# l-drv_h2-smd-001.net
KiCad netlist of a schematic drawn in EAGLE
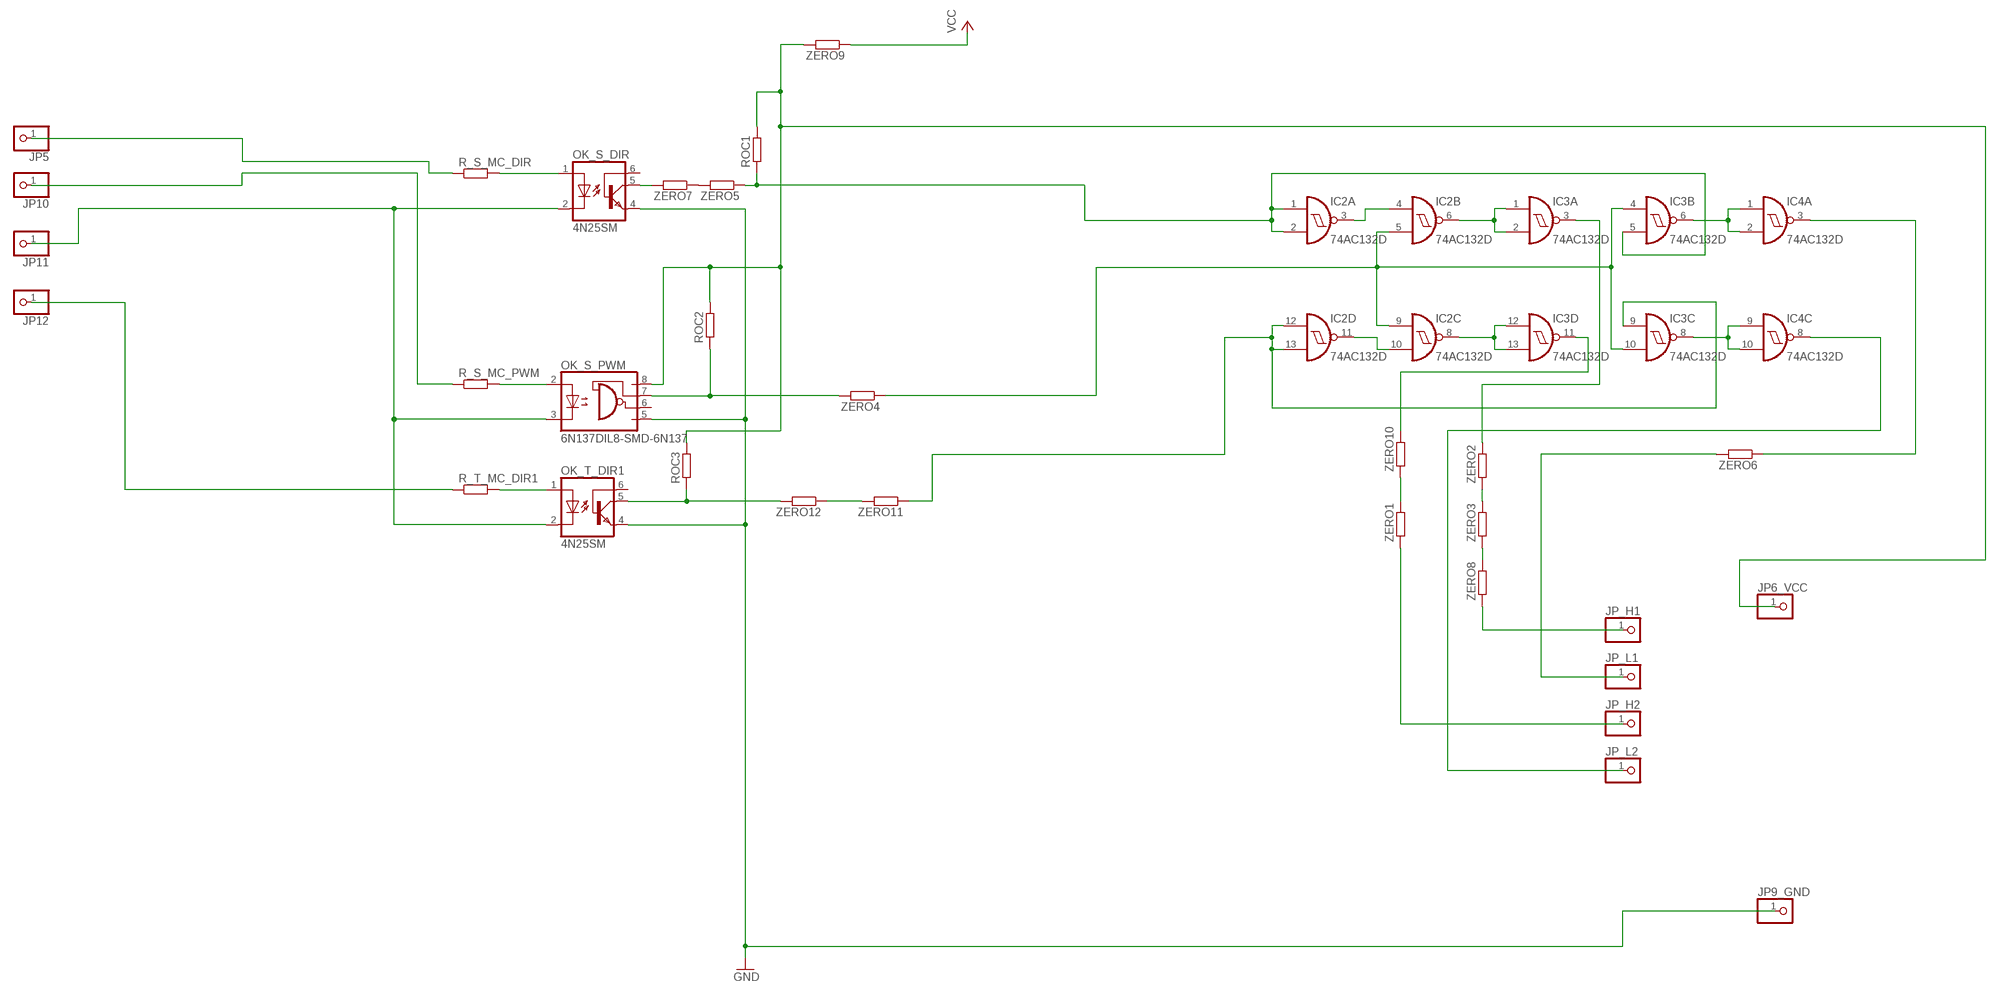
[diagram p0: schematic, sheet 1]

(export (version "E")
  (design (tool "Eeschema 10.0.6"))
  (components
    (comp (ref "IC2")
      (value "74AC132D")
      (footprint "eagle-import:SO14")
      (libsource (lib "eagle-import") (part "74132DAC"))
    )
    (comp (ref "IC3")
      (value "74AC132D")
      (footprint "eagle-import:SO14")
      (libsource (lib "eagle-import") (part "74132DAC"))
    )
    (comp (ref "IC4")
      (value "74AC132D")
      (footprint "eagle-import:SO14")
      (libsource (lib "eagle-import") (part "74132DAC"))
    )
    (comp (ref "JP5")
      (value "PINHD-1X1")
      (footprint "eagle-import:1X01")
      (libsource (lib "eagle-import") (part "PINHD-1X1"))
    )
    (comp (ref "JP6_VCC")
      (value "PINHD-1X1")
      (footprint "eagle-import:1X01")
      (libsource (lib "eagle-import") (part "PINHD-1X1"))
    )
    (comp (ref "JP9_GND")
      (value "PINHD-1X1")
      (footprint "eagle-import:1X01")
      (libsource (lib "eagle-import") (part "PINHD-1X1"))
    )
    (comp (ref "JP10")
      (value "PINHD-1X1")
      (footprint "eagle-import:1X01")
      (libsource (lib "eagle-import") (part "PINHD-1X1"))
    )
    (comp (ref "JP11")
      (value "PINHD-1X1")
      (footprint "eagle-import:1X01")
      (libsource (lib "eagle-import") (part "PINHD-1X1"))
    )
    (comp (ref "JP12")
      (value "PINHD-1X1")
      (footprint "eagle-import:1X01")
      (libsource (lib "eagle-import") (part "PINHD-1X1"))
    )
    (comp (ref "JP_H1")
      (value "PINHD-1X1")
      (footprint "eagle-import:1X01")
      (libsource (lib "eagle-import") (part "PINHD-1X1"))
    )
    (comp (ref "JP_H2")
      (value "PINHD-1X1")
      (footprint "eagle-import:1X01")
      (libsource (lib "eagle-import") (part "PINHD-1X1"))
    )
    (comp (ref "JP_L1")
      (value "PINHD-1X1")
      (footprint "eagle-import:1X01")
      (libsource (lib "eagle-import") (part "PINHD-1X1"))
    )
    (comp (ref "JP_L2")
      (value "PINHD-1X1")
      (footprint "eagle-import:1X01")
      (libsource (lib "eagle-import") (part "PINHD-1X1"))
    )
    (comp (ref "OK_S_DIR")
      (value "4N25SM")
      (footprint "eagle-import:DIL6-SMD")
      (fields (field (name "MF") "FAIRCHILD SEMICONDUCTOR"))
      (libsource (lib "eagle-import") (part "4N?MS25"))
    )
    (comp (ref "OK_S_PWM")
      (value "6N137DIL8-SMD-6N137")
      (footprint "eagle-import:DIL8-SMD")
      (libsource (lib "eagle-import") (part "6N137DIL8-SMD-6N137"))
    )
    (comp (ref "OK_T_DIR1")
      (value "4N25SM")
      (footprint "eagle-import:DIL6-SMD")
      (fields (field (name "MF") "FAIRCHILD SEMICONDUCTOR"))
      (libsource (lib "eagle-import") (part "4N?MS25"))
    )
    (comp (ref "ROC1")
      (value "R-EU_R1206")
      (footprint "eagle-import:R1206")
      (libsource (lib "eagle-import") (part "R-EU_R1206"))
    )
    (comp (ref "ROC2")
      (value "R-EU_R1206")
      (footprint "eagle-import:R1206")
      (libsource (lib "eagle-import") (part "R-EU_R1206"))
    )
    (comp (ref "ROC3")
      (value "R-EU_R1206")
      (footprint "eagle-import:R1206")
      (libsource (lib "eagle-import") (part "R-EU_R1206"))
    )
    (comp (ref "R_S_MC_DIR")
      (value "R-EU_R1206")
      (footprint "eagle-import:R1206")
      (libsource (lib "eagle-import") (part "R-EU_R1206"))
    )
    (comp (ref "R_S_MC_PWM")
      (value "R-EU_R1206")
      (footprint "eagle-import:R1206")
      (libsource (lib "eagle-import") (part "R-EU_R1206"))
    )
    (comp (ref "R_T_MC_DIR1")
      (value "R-EU_R1206")
      (footprint "eagle-import:R1206")
      (libsource (lib "eagle-import") (part "R-EU_R1206"))
    )
    (comp (ref "ZERO1")
      (value "R-EU_R1206")
      (footprint "eagle-import:R1206")
      (libsource (lib "eagle-import") (part "R-EU_R1206"))
    )
    (comp (ref "ZERO2")
      (value "R-EU_R1206")
      (footprint "eagle-import:R1206")
      (libsource (lib "eagle-import") (part "R-EU_R1206"))
    )
    (comp (ref "ZERO3")
      (value "R-EU_R1206")
      (footprint "eagle-import:R1206")
      (libsource (lib "eagle-import") (part "R-EU_R1206"))
    )
    (comp (ref "ZERO4")
      (value "R-EU_R1206")
      (footprint "eagle-import:R1206")
      (libsource (lib "eagle-import") (part "R-EU_R1206"))
    )
    (comp (ref "ZERO5")
      (value "R-EU_R1206")
      (footprint "eagle-import:R1206")
      (libsource (lib "eagle-import") (part "R-EU_R1206"))
    )
    (comp (ref "ZERO6")
      (value "R-EU_R1206")
      (footprint "eagle-import:R1206")
      (libsource (lib "eagle-import") (part "R-EU_R1206"))
    )
    (comp (ref "ZERO7")
      (value "R-EU_R1206")
      (footprint "eagle-import:R1206")
      (libsource (lib "eagle-import") (part "R-EU_R1206"))
    )
    (comp (ref "ZERO8")
      (value "R-EU_R1206")
      (footprint "eagle-import:R1206")
      (libsource (lib "eagle-import") (part "R-EU_R1206"))
    )
    (comp (ref "ZERO9")
      (value "R-EU_R1206")
      (footprint "eagle-import:R1206")
      (libsource (lib "eagle-import") (part "R-EU_R1206"))
    )
    (comp (ref "ZERO10")
      (value "R-EU_R1206")
      (footprint "eagle-import:R1206")
      (libsource (lib "eagle-import") (part "R-EU_R1206"))
    )
    (comp (ref "ZERO11")
      (value "R-EU_R1206")
      (footprint "eagle-import:R1206")
      (libsource (lib "eagle-import") (part "R-EU_R1206"))
    )
    (comp (ref "ZERO12")
      (value "R-EU_R1206")
      (footprint "eagle-import:R1206")
      (libsource (lib "eagle-import") (part "R-EU_R1206"))
    )
  )
  (nets
    (net (code "1") (name "GND") (class "Default")
      (node (ref "JP9_GND") (pin "1") (pinfunction "1_1") (pintype "passive"))
      (node (ref "OK_S_DIR") (pin "4") (pinfunction "EMI_4") (pintype "passive"))
      (node (ref "OK_S_PWM") (pin "5") (pinfunction "GND_5") (pintype "passive"))
      (node (ref "OK_T_DIR1") (pin "4") (pinfunction "EMI_4") (pintype "passive"))
    )
    (net (code "2") (name "Net-(IC2A-I0)") (class "Default")
      (node (ref "IC2") (pin "1") (pinfunction "I0_1") (pintype "input"))
      (node (ref "IC2") (pin "2") (pinfunction "I1_2") (pintype "input"))
      (node (ref "IC3") (pin "5") (pinfunction "I1_5") (pintype "input"))
      (node (ref "ROC1") (pin "1") (pinfunction "1_1") (pintype "passive"))
      (node (ref "ZERO5") (pin "1") (pinfunction "1_1") (pintype "passive"))
    )
    (net (code "3") (name "Net-(IC2A-O)") (class "Default")
      (node (ref "IC2") (pin "3") (pinfunction "O_3") (pintype "output"))
      (node (ref "IC2") (pin "4") (pinfunction "I0_4") (pintype "input"))
    )
    (net (code "4") (name "Net-(IC2B-I1)") (class "Default")
      (node (ref "IC2") (pin "5") (pinfunction "I1_5") (pintype "input"))
      (node (ref "IC2") (pin "9") (pinfunction "I0_9") (pintype "input"))
      (node (ref "IC3") (pin "10") (pinfunction "I1_10") (pintype "input"))
      (node (ref "IC3") (pin "4") (pinfunction "I0_4") (pintype "input"))
      (node (ref "ZERO4") (pin "1") (pinfunction "1_1") (pintype "passive"))
    )
    (net (code "5") (name "Net-(IC2B-O)") (class "Default")
      (node (ref "IC2") (pin "6") (pinfunction "O_6") (pintype "output"))
      (node (ref "IC3") (pin "1") (pinfunction "I0_1") (pintype "input"))
      (node (ref "IC3") (pin "2") (pinfunction "I1_2") (pintype "input"))
    )
    (net (code "6") (name "Net-(IC2C-I1)") (class "Default")
      (node (ref "IC2") (pin "10") (pinfunction "I1_10") (pintype "input"))
      (node (ref "IC2") (pin "11") (pinfunction "O_11") (pintype "output"))
    )
    (net (code "7") (name "Net-(IC2C-O)") (class "Default")
      (node (ref "IC2") (pin "8") (pinfunction "O_8") (pintype "output"))
      (node (ref "IC3") (pin "12") (pinfunction "I0_12") (pintype "input"))
      (node (ref "IC3") (pin "13") (pinfunction "I1_13") (pintype "input"))
    )
    (net (code "8") (name "Net-(IC2D-I0)") (class "Default")
      (node (ref "IC2") (pin "12") (pinfunction "I0_12") (pintype "input"))
      (node (ref "IC2") (pin "13") (pinfunction "I1_13") (pintype "input"))
      (node (ref "IC3") (pin "9") (pinfunction "I0_9") (pintype "input"))
      (node (ref "ZERO11") (pin "1") (pinfunction "1_1") (pintype "passive"))
    )
    (net (code "9") (name "Net-(IC3A-O)") (class "Default")
      (node (ref "IC3") (pin "3") (pinfunction "O_3") (pintype "output"))
      (node (ref "ZERO2") (pin "2") (pinfunction "2_2") (pintype "passive"))
    )
    (net (code "10") (name "Net-(IC3B-O)") (class "Default")
      (node (ref "IC3") (pin "6") (pinfunction "O_6") (pintype "output"))
      (node (ref "IC4") (pin "1") (pinfunction "I0_1") (pintype "input"))
      (node (ref "IC4") (pin "2") (pinfunction "I1_2") (pintype "input"))
    )
    (net (code "11") (name "Net-(IC3C-O)") (class "Default")
      (node (ref "IC3") (pin "8") (pinfunction "O_8") (pintype "output"))
      (node (ref "IC4") (pin "10") (pinfunction "I1_10") (pintype "input"))
      (node (ref "IC4") (pin "9") (pinfunction "I0_9") (pintype "input"))
    )
    (net (code "12") (name "Net-(IC3D-O)") (class "Default")
      (node (ref "IC3") (pin "11") (pinfunction "O_11") (pintype "output"))
      (node (ref "ZERO10") (pin "2") (pinfunction "2_2") (pintype "passive"))
    )
    (net (code "13") (name "Net-(IC4A-O)") (class "Default")
      (node (ref "IC4") (pin "3") (pinfunction "O_3") (pintype "output"))
      (node (ref "ZERO6") (pin "1") (pinfunction "1_1") (pintype "passive"))
    )
    (net (code "14") (name "Net-(IC4C-O)") (class "Default")
      (node (ref "IC4") (pin "8") (pinfunction "O_8") (pintype "output"))
      (node (ref "JP_L2") (pin "1") (pinfunction "1_1") (pintype "passive"))
    )
    (net (code "15") (name "Net-(JP5-Pad1)") (class "Default")
      (node (ref "JP5") (pin "1") (pinfunction "1_1") (pintype "passive"))
      (node (ref "R_S_MC_DIR") (pin "1") (pinfunction "1_1") (pintype "passive"))
    )
    (net (code "16") (name "Net-(JP10-Pad1)") (class "Default")
      (node (ref "JP10") (pin "1") (pinfunction "1_1") (pintype "passive"))
      (node (ref "R_S_MC_PWM") (pin "1") (pinfunction "1_1") (pintype "passive"))
    )
    (net (code "17") (name "Net-(JP12-Pad1)") (class "Default")
      (node (ref "JP12") (pin "1") (pinfunction "1_1") (pintype "passive"))
      (node (ref "R_T_MC_DIR1") (pin "1") (pinfunction "1_1") (pintype "passive"))
    )
    (net (code "18") (name "Net-(JP_H1-Pad1)") (class "Default")
      (node (ref "JP_H1") (pin "1") (pinfunction "1_1") (pintype "passive"))
      (node (ref "ZERO8") (pin "1") (pinfunction "1_1") (pintype "passive"))
    )
    (net (code "19") (name "Net-(JP_H2-Pad1)") (class "Default")
      (node (ref "JP_H2") (pin "1") (pinfunction "1_1") (pintype "passive"))
      (node (ref "ZERO1") (pin "1") (pinfunction "1_1") (pintype "passive"))
    )
    (net (code "20") (name "Net-(JP_L1-Pad1)") (class "Default")
      (node (ref "JP_L1") (pin "1") (pinfunction "1_1") (pintype "passive"))
      (node (ref "ZERO6") (pin "2") (pinfunction "2_2") (pintype "passive"))
    )
    (net (code "21") (name "Net-(OK_S_DIR-A)") (class "Default")
      (node (ref "OK_S_DIR") (pin "1") (pinfunction "A_1") (pintype "passive"))
      (node (ref "R_S_MC_DIR") (pin "2") (pinfunction "2_2") (pintype "passive"))
    )
    (net (code "22") (name "Net-(OK_S_DIR-C)") (class "Default")
      (node (ref "JP11") (pin "1") (pinfunction "1_1") (pintype "passive"))
      (node (ref "OK_S_DIR") (pin "2") (pinfunction "C_2") (pintype "passive"))
      (node (ref "OK_S_PWM") (pin "3") (pinfunction "C_3") (pintype "passive"))
      (node (ref "OK_T_DIR1") (pin "2") (pinfunction "C_2") (pintype "passive"))
    )
    (net (code "23") (name "Net-(OK_S_DIR-COL)") (class "Default")
      (node (ref "OK_S_DIR") (pin "5") (pinfunction "COL_5") (pintype "passive"))
      (node (ref "ZERO7") (pin "2") (pinfunction "2_2") (pintype "passive"))
    )
    (net (code "24") (name "Net-(OK_S_PWM-A)") (class "Default")
      (node (ref "OK_S_PWM") (pin "2") (pinfunction "A_2") (pintype "passive"))
      (node (ref "R_S_MC_PWM") (pin "2") (pinfunction "2_2") (pintype "passive"))
    )
    (net (code "25") (name "Net-(OK_S_PWM-VCC)") (class "Default")
      (node (ref "JP6_VCC") (pin "1") (pinfunction "1_1") (pintype "passive"))
      (node (ref "OK_S_PWM") (pin "8") (pinfunction "VCC_8") (pintype "passive"))
      (node (ref "ROC1") (pin "2") (pinfunction "2_2") (pintype "passive"))
      (node (ref "ROC2") (pin "2") (pinfunction "2_2") (pintype "passive"))
      (node (ref "ROC3") (pin "2") (pinfunction "2_2") (pintype "passive"))
      (node (ref "ZERO9") (pin "2") (pinfunction "2_2") (pintype "passive"))
    )
    (net (code "26") (name "Net-(OK_S_PWM-VE)") (class "Default")
      (node (ref "OK_S_PWM") (pin "7") (pinfunction "VE_7") (pintype "passive"))
      (node (ref "ROC2") (pin "1") (pinfunction "1_1") (pintype "passive"))
      (node (ref "ZERO4") (pin "2") (pinfunction "2_2") (pintype "passive"))
    )
    (net (code "27") (name "Net-(OK_T_DIR1-A)") (class "Default")
      (node (ref "OK_T_DIR1") (pin "1") (pinfunction "A_1") (pintype "passive"))
      (node (ref "R_T_MC_DIR1") (pin "2") (pinfunction "2_2") (pintype "passive"))
    )
    (net (code "28") (name "Net-(OK_T_DIR1-COL)") (class "Default")
      (node (ref "OK_T_DIR1") (pin "5") (pinfunction "COL_5") (pintype "passive"))
      (node (ref "ROC3") (pin "1") (pinfunction "1_1") (pintype "passive"))
      (node (ref "ZERO12") (pin "2") (pinfunction "2_2") (pintype "passive"))
    )
    (net (code "29") (name "Net-(ZERO1-Pad2)") (class "Default")
      (node (ref "ZERO1") (pin "2") (pinfunction "2_2") (pintype "passive"))
      (node (ref "ZERO10") (pin "1") (pinfunction "1_1") (pintype "passive"))
    )
    (net (code "30") (name "Net-(ZERO2-Pad1)") (class "Default")
      (node (ref "ZERO2") (pin "1") (pinfunction "1_1") (pintype "passive"))
      (node (ref "ZERO3") (pin "2") (pinfunction "2_2") (pintype "passive"))
    )
    (net (code "31") (name "Net-(ZERO3-Pad1)") (class "Default")
      (node (ref "ZERO3") (pin "1") (pinfunction "1_1") (pintype "passive"))
      (node (ref "ZERO8") (pin "2") (pinfunction "2_2") (pintype "passive"))
    )
    (net (code "32") (name "Net-(ZERO5-Pad2)") (class "Default")
      (node (ref "ZERO5") (pin "2") (pinfunction "2_2") (pintype "passive"))
      (node (ref "ZERO7") (pin "1") (pinfunction "1_1") (pintype "passive"))
    )
    (net (code "33") (name "Net-(ZERO11-Pad2)") (class "Default")
      (node (ref "ZERO11") (pin "2") (pinfunction "2_2") (pintype "passive"))
      (node (ref "ZERO12") (pin "1") (pinfunction "1_1") (pintype "passive"))
    )
    (net (code "34") (name "VCC") (class "Default")
      (node (ref "ZERO9") (pin "1") (pinfunction "1_1") (pintype "passive"))
    )
    (net (code "35") (name "unconnected-(OK_S_DIR-BAS-Pad6)") (class "Default")
      (node (ref "OK_S_DIR") (pin "6") (pinfunction "BAS_6") (pintype "passive"))
    )
    (net (code "36") (name "unconnected-(OK_S_PWM-VO-Pad6)") (class "Default")
      (node (ref "OK_S_PWM") (pin "6") (pinfunction "VO_6") (pintype "passive"))
    )
    (net (code "37") (name "unconnected-(OK_T_DIR1-BAS-Pad6)") (class "Default")
      (node (ref "OK_T_DIR1") (pin "6") (pinfunction "BAS_6") (pintype "passive"))
    )
  )
)
